# LucidVRSensorPCB_Side_2part.net
KiCad netlist of a schematic drawn in EasyEDA
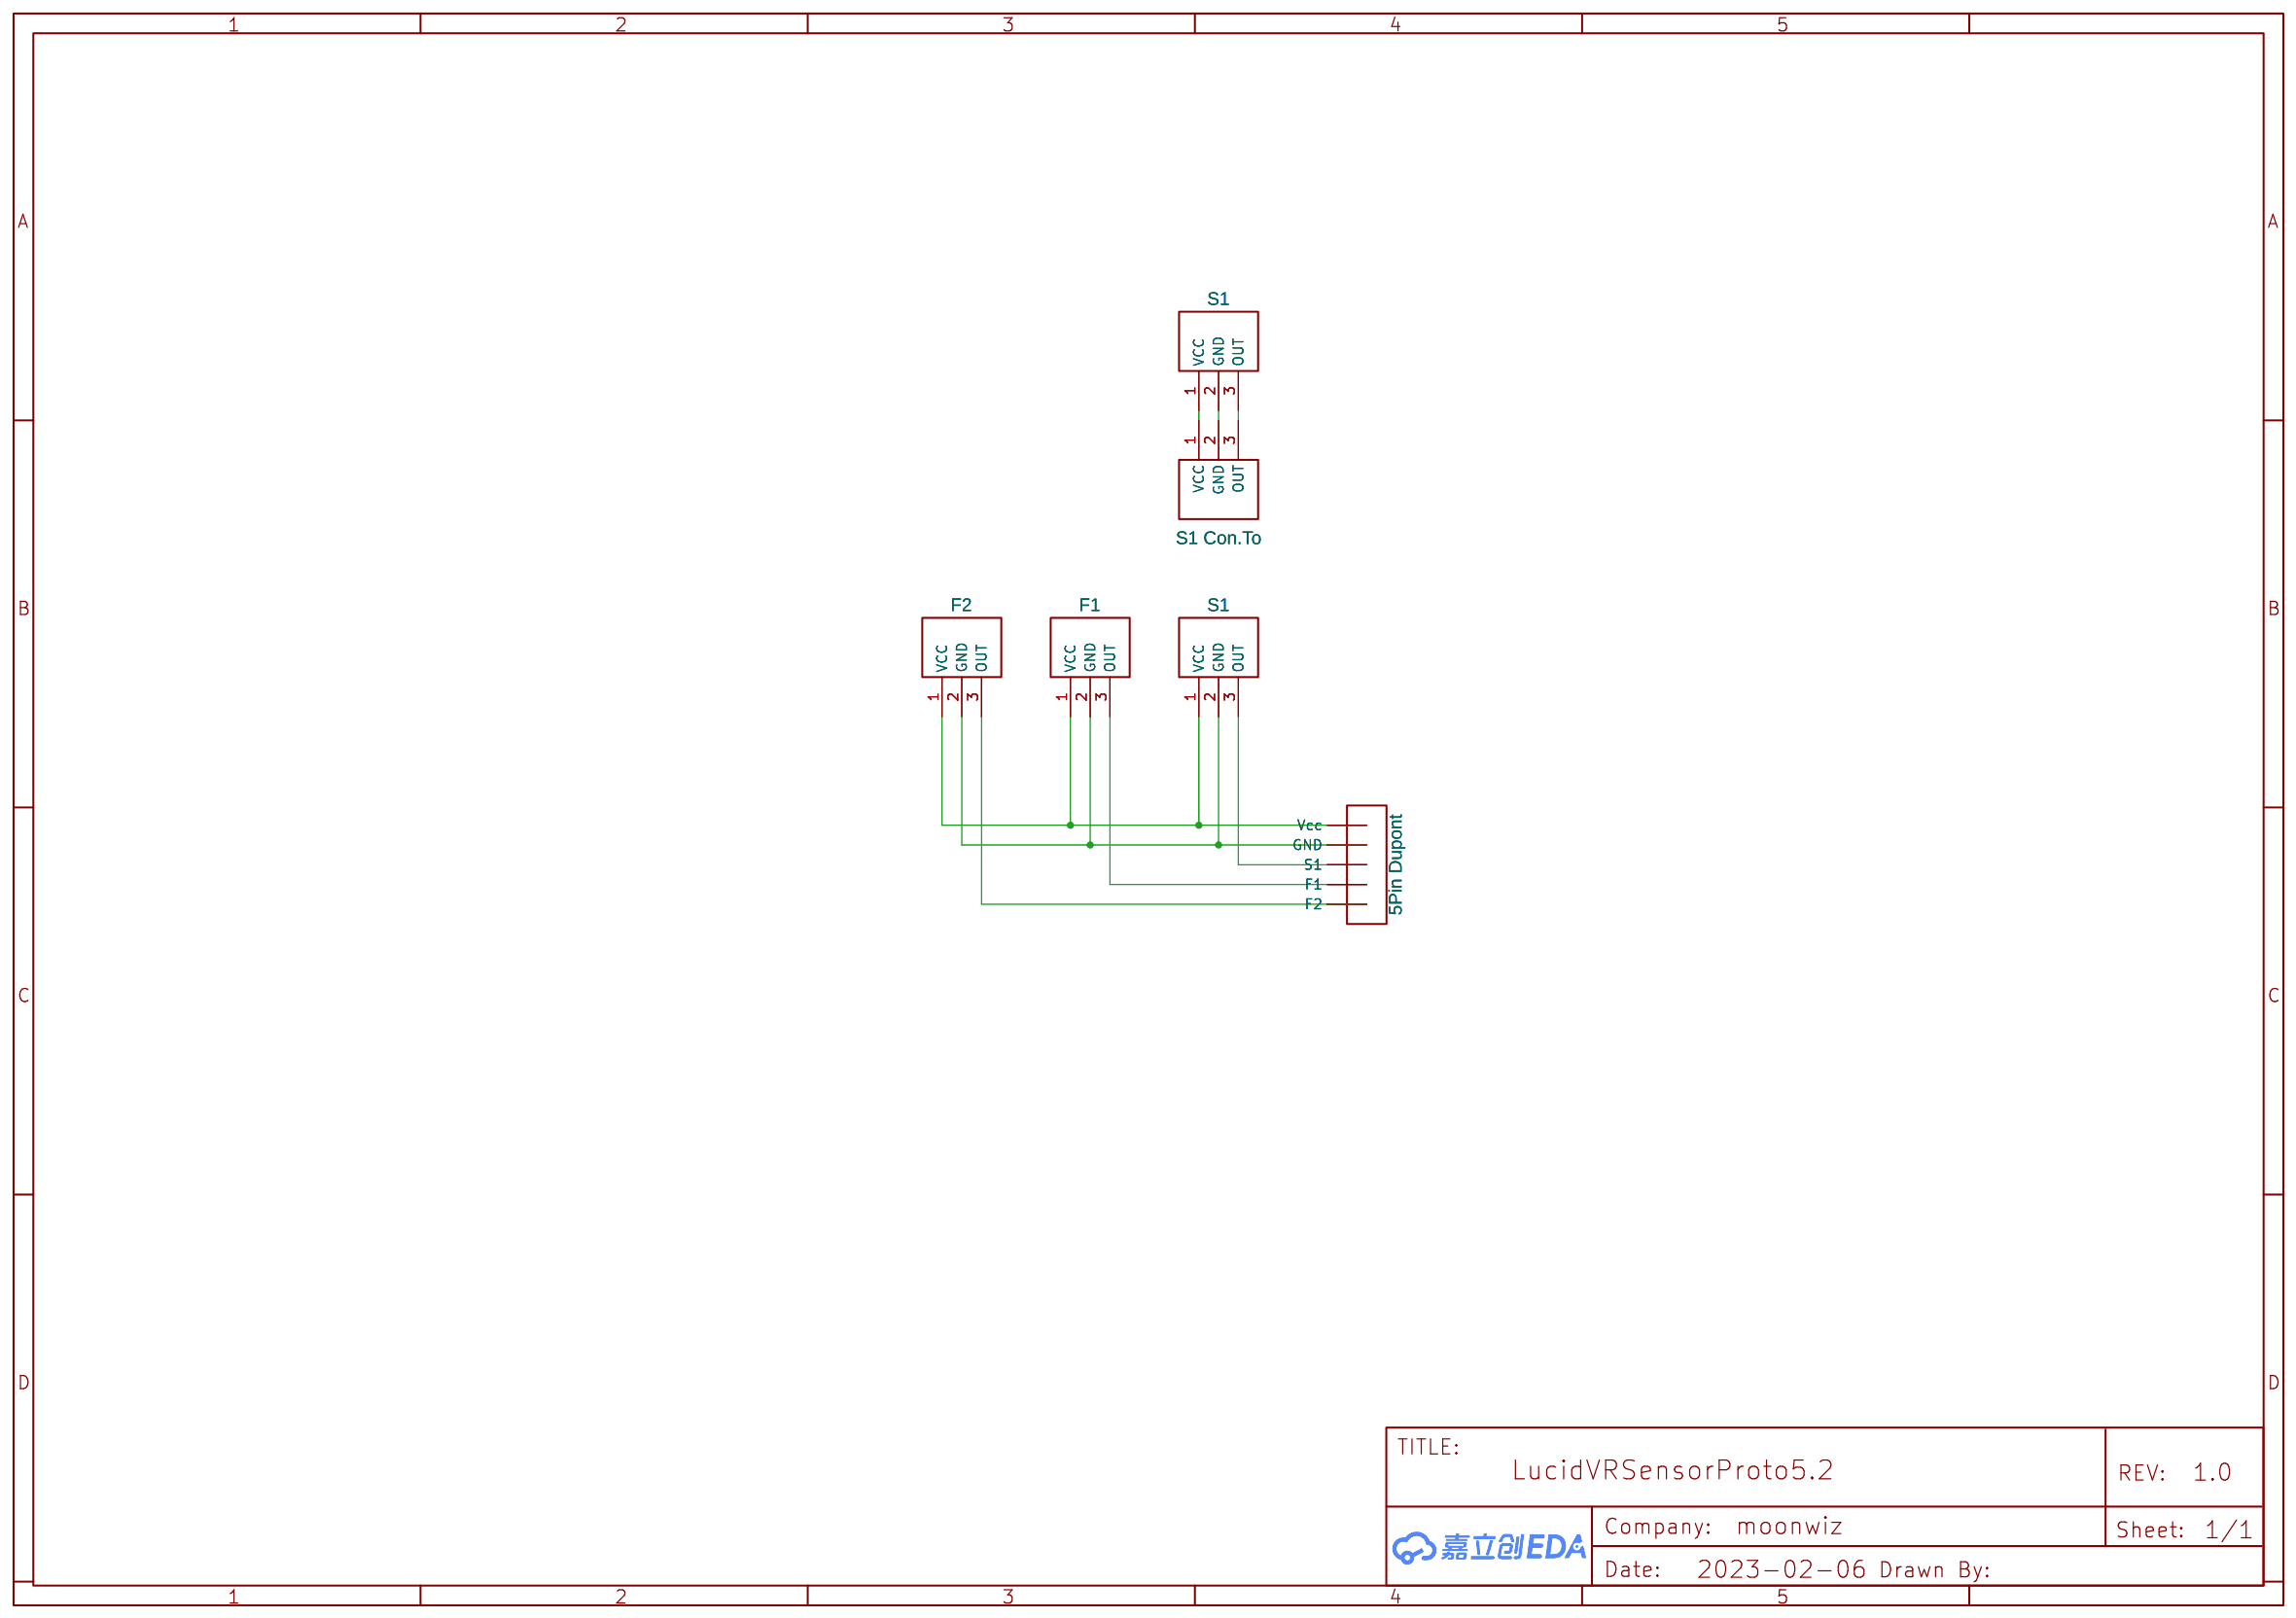
[diagram p0: schematic sheet]

(export (version "E")
  (design (tool "Eeschema 10.0.6"))
  (components
    (comp (ref "S1")
      (value "S1 Con.To")
      (fields (field (name "BOM_Manufacturer Part") "OH49E") (field (name "BOM_Supplier Part") "C81386"))
      (libsource (lib "") (part "OH49E_1"))
    )
    (comp (ref "S2")
      (value "S1")
      (fields (field (name "BOM_Manufacturer Part") "OH49E") (field (name "BOM_Supplier Part") "C81386"))
      (libsource (lib "") (part "OH49E"))
    )
    (comp (ref "S4")
      (value "F1")
      (fields (field (name "BOM_Manufacturer Part") "OH49E") (field (name "BOM_Supplier Part") "C81386"))
      (libsource (lib "") (part "OH49E"))
    )
    (comp (ref "S5")
      (value "S1")
      (fields (field (name "BOM_Manufacturer Part") "OH49E") (field (name "BOM_Supplier Part") "C81386"))
      (libsource (lib "") (part "OH49E"))
    )
    (comp (ref "S6")
      (value "F2")
      (fields (field (name "BOM_Manufacturer Part") "OH49E") (field (name "BOM_Supplier Part") "C81386"))
      (libsource (lib "") (part "OH49E"))
    )
    (comp (ref "U3") (value "5Pin Dupont") (libsource (lib "") (part "5Pin Dupont")))
  )
  (nets
    (net (code "1") (name "Net-(S1-GND)") (class "Default")
      (node (ref "S1") (pin "2") (pinfunction "GND_2") (pintype "unspecified"))
      (node (ref "S5") (pin "2") (pinfunction "GND_2") (pintype "unspecified"))
    )
    (net (code "2") (name "Net-(S1-OUT)") (class "Default")
      (node (ref "S1") (pin "3") (pinfunction "OUT_3") (pintype "unspecified"))
      (node (ref "S5") (pin "3") (pinfunction "OUT_3") (pintype "unspecified"))
    )
    (net (code "3") (name "Net-(S1-VCC)") (class "Default")
      (node (ref "S1") (pin "1") (pinfunction "VCC_1") (pintype "unspecified"))
      (node (ref "S5") (pin "1") (pinfunction "VCC_1") (pintype "unspecified"))
    )
    (net (code "4") (name "Net-(S2-GND)") (class "Default")
      (node (ref "S2") (pin "2") (pinfunction "GND_2") (pintype "unspecified"))
      (node (ref "S4") (pin "2") (pinfunction "GND_2") (pintype "unspecified"))
      (node (ref "S6") (pin "2") (pinfunction "GND_2") (pintype "unspecified"))
      (node (ref "U3") (pin "2") (pinfunction "GND_2") (pintype "unspecified"))
    )
    (net (code "5") (name "Net-(S2-OUT)") (class "Default")
      (node (ref "S2") (pin "3") (pinfunction "OUT_3") (pintype "unspecified"))
      (node (ref "U3") (pin "3") (pinfunction "S1_3") (pintype "unspecified"))
    )
    (net (code "6") (name "Net-(S2-VCC)") (class "Default")
      (node (ref "S2") (pin "1") (pinfunction "VCC_1") (pintype "unspecified"))
      (node (ref "S4") (pin "1") (pinfunction "VCC_1") (pintype "unspecified"))
      (node (ref "S6") (pin "1") (pinfunction "VCC_1") (pintype "unspecified"))
      (node (ref "U3") (pin "1") (pinfunction "Vcc_1") (pintype "unspecified"))
    )
    (net (code "7") (name "Net-(S4-OUT)") (class "Default")
      (node (ref "S4") (pin "3") (pinfunction "OUT_3") (pintype "unspecified"))
      (node (ref "U3") (pin "4") (pinfunction "F1_4") (pintype "unspecified"))
    )
    (net (code "8") (name "Net-(S6-OUT)") (class "Default")
      (node (ref "S6") (pin "3") (pinfunction "OUT_3") (pintype "unspecified"))
      (node (ref "U3") (pin "5") (pinfunction "F2_5") (pintype "unspecified"))
    )
  )
)
